# relays3.net
KiCad netlist of a schematic drawn in Altium Designer
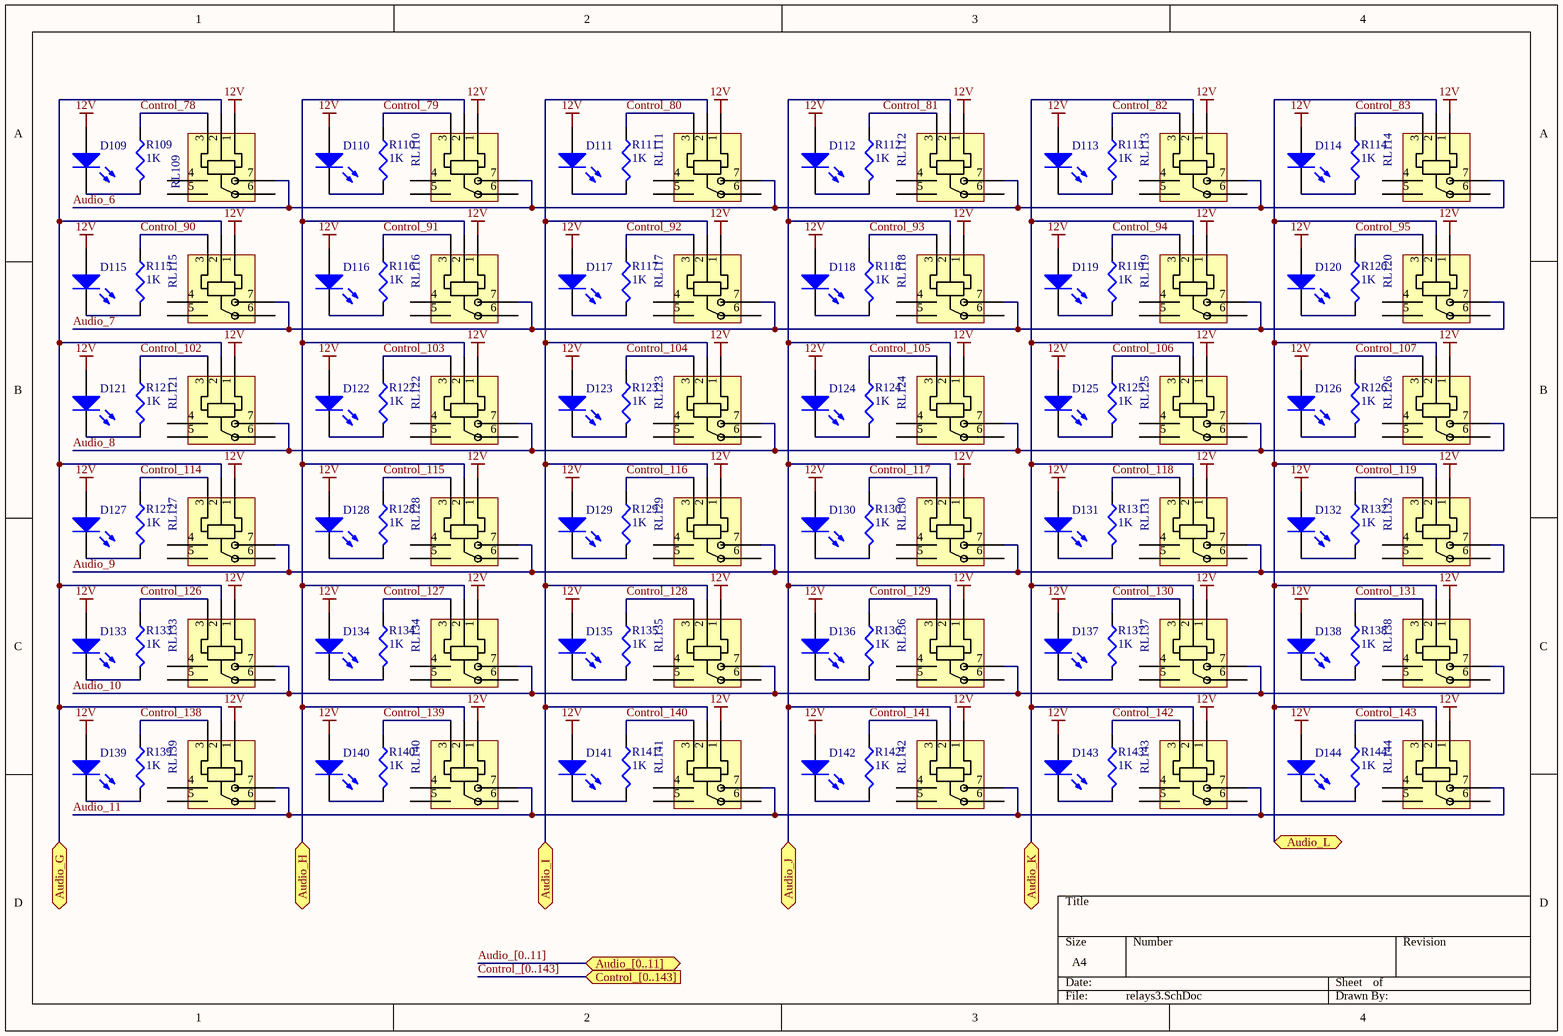
[diagram p0: relays3.SchDoc]

(export (version "E")
  (design (tool "Eeschema 10.0.6"))
  (components
    (comp (ref "D109")
      (value "LED0")
      (footprint "LED_round_5mm")
      (description "Typical INFRARED GaAs LED")
      (libsource (lib "Miscellaneous Devices") (part "LED0"))
    )
    (comp (ref "D110")
      (value "LED0")
      (footprint "LED_round_5mm")
      (description "Typical INFRARED GaAs LED")
      (libsource (lib "Miscellaneous Devices") (part "LED0"))
    )
    (comp (ref "D111")
      (value "LED0")
      (footprint "LED_round_5mm")
      (description "Typical INFRARED GaAs LED")
      (libsource (lib "Miscellaneous Devices") (part "LED0"))
    )
    (comp (ref "D112")
      (value "LED0")
      (footprint "LED_round_5mm")
      (description "Typical INFRARED GaAs LED")
      (libsource (lib "Miscellaneous Devices") (part "LED0"))
    )
    (comp (ref "D113")
      (value "LED0")
      (footprint "LED_round_5mm")
      (description "Typical INFRARED GaAs LED")
      (libsource (lib "Miscellaneous Devices") (part "LED0"))
    )
    (comp (ref "D114")
      (value "LED0")
      (footprint "LED_round_5mm")
      (description "Typical INFRARED GaAs LED")
      (libsource (lib "Miscellaneous Devices") (part "LED0"))
    )
    (comp (ref "D115")
      (value "LED0")
      (footprint "LED_round_5mm")
      (description "Typical INFRARED GaAs LED")
      (libsource (lib "Miscellaneous Devices") (part "LED0"))
    )
    (comp (ref "D116")
      (value "LED0")
      (footprint "LED_round_5mm")
      (description "Typical INFRARED GaAs LED")
      (libsource (lib "Miscellaneous Devices") (part "LED0"))
    )
    (comp (ref "D117")
      (value "LED0")
      (footprint "LED_round_5mm")
      (description "Typical INFRARED GaAs LED")
      (libsource (lib "Miscellaneous Devices") (part "LED0"))
    )
    (comp (ref "D118")
      (value "LED0")
      (footprint "LED_round_5mm")
      (description "Typical INFRARED GaAs LED")
      (libsource (lib "Miscellaneous Devices") (part "LED0"))
    )
    (comp (ref "D119")
      (value "LED0")
      (footprint "LED_round_5mm")
      (description "Typical INFRARED GaAs LED")
      (libsource (lib "Miscellaneous Devices") (part "LED0"))
    )
    (comp (ref "D120")
      (value "LED0")
      (footprint "LED_round_5mm")
      (description "Typical INFRARED GaAs LED")
      (libsource (lib "Miscellaneous Devices") (part "LED0"))
    )
    (comp (ref "D121")
      (value "LED0")
      (footprint "LED_round_5mm")
      (description "Typical INFRARED GaAs LED")
      (libsource (lib "Miscellaneous Devices") (part "LED0"))
    )
    (comp (ref "D122")
      (value "LED0")
      (footprint "LED_round_5mm")
      (description "Typical INFRARED GaAs LED")
      (libsource (lib "Miscellaneous Devices") (part "LED0"))
    )
    (comp (ref "D123")
      (value "LED0")
      (footprint "LED_round_5mm")
      (description "Typical INFRARED GaAs LED")
      (libsource (lib "Miscellaneous Devices") (part "LED0"))
    )
    (comp (ref "D124")
      (value "LED0")
      (footprint "LED_round_5mm")
      (description "Typical INFRARED GaAs LED")
      (libsource (lib "Miscellaneous Devices") (part "LED0"))
    )
    (comp (ref "D125")
      (value "LED0")
      (footprint "LED_round_5mm")
      (description "Typical INFRARED GaAs LED")
      (libsource (lib "Miscellaneous Devices") (part "LED0"))
    )
    (comp (ref "D126")
      (value "LED0")
      (footprint "LED_round_5mm")
      (description "Typical INFRARED GaAs LED")
      (libsource (lib "Miscellaneous Devices") (part "LED0"))
    )
    (comp (ref "D127")
      (value "LED0")
      (footprint "LED_round_5mm")
      (description "Typical INFRARED GaAs LED")
      (libsource (lib "Miscellaneous Devices") (part "LED0"))
    )
    (comp (ref "D128")
      (value "LED0")
      (footprint "LED_round_5mm")
      (description "Typical INFRARED GaAs LED")
      (libsource (lib "Miscellaneous Devices") (part "LED0"))
    )
    (comp (ref "D129")
      (value "LED0")
      (footprint "LED_round_5mm")
      (description "Typical INFRARED GaAs LED")
      (libsource (lib "Miscellaneous Devices") (part "LED0"))
    )
    (comp (ref "D130")
      (value "LED0")
      (footprint "LED_round_5mm")
      (description "Typical INFRARED GaAs LED")
      (libsource (lib "Miscellaneous Devices") (part "LED0"))
    )
    (comp (ref "D131")
      (value "LED0")
      (footprint "LED_round_5mm")
      (description "Typical INFRARED GaAs LED")
      (libsource (lib "Miscellaneous Devices") (part "LED0"))
    )
    (comp (ref "D132")
      (value "LED0")
      (footprint "LED_round_5mm")
      (description "Typical INFRARED GaAs LED")
      (libsource (lib "Miscellaneous Devices") (part "LED0"))
    )
    (comp (ref "D133")
      (value "LED0")
      (footprint "LED_round_5mm")
      (description "Typical INFRARED GaAs LED")
      (libsource (lib "Miscellaneous Devices") (part "LED0"))
    )
    (comp (ref "D134")
      (value "LED0")
      (footprint "LED_round_5mm")
      (description "Typical INFRARED GaAs LED")
      (libsource (lib "Miscellaneous Devices") (part "LED0"))
    )
    (comp (ref "D135")
      (value "LED0")
      (footprint "LED_round_5mm")
      (description "Typical INFRARED GaAs LED")
      (libsource (lib "Miscellaneous Devices") (part "LED0"))
    )
    (comp (ref "D136")
      (value "LED0")
      (footprint "LED_round_5mm")
      (description "Typical INFRARED GaAs LED")
      (libsource (lib "Miscellaneous Devices") (part "LED0"))
    )
    (comp (ref "D137")
      (value "LED0")
      (footprint "LED_round_5mm")
      (description "Typical INFRARED GaAs LED")
      (libsource (lib "Miscellaneous Devices") (part "LED0"))
    )
    (comp (ref "D138")
      (value "LED0")
      (footprint "LED_round_5mm")
      (description "Typical INFRARED GaAs LED")
      (libsource (lib "Miscellaneous Devices") (part "LED0"))
    )
    (comp (ref "D139")
      (value "LED0")
      (footprint "LED_round_5mm")
      (description "Typical INFRARED GaAs LED")
      (libsource (lib "Miscellaneous Devices") (part "LED0"))
    )
    (comp (ref "D140")
      (value "LED0")
      (footprint "LED_round_5mm")
      (description "Typical INFRARED GaAs LED")
      (libsource (lib "Miscellaneous Devices") (part "LED0"))
    )
    (comp (ref "D141")
      (value "LED0")
      (footprint "LED_round_5mm")
      (description "Typical INFRARED GaAs LED")
      (libsource (lib "Miscellaneous Devices") (part "LED0"))
    )
    (comp (ref "D142")
      (value "LED0")
      (footprint "LED_round_5mm")
      (description "Typical INFRARED GaAs LED")
      (libsource (lib "Miscellaneous Devices") (part "LED0"))
    )
    (comp (ref "D143")
      (value "LED0")
      (footprint "LED_round_5mm")
      (description "Typical INFRARED GaAs LED")
      (libsource (lib "Miscellaneous Devices") (part "LED0"))
    )
    (comp (ref "D144")
      (value "LED0")
      (footprint "LED_round_5mm")
      (description "Typical INFRARED GaAs LED")
      (libsource (lib "Miscellaneous Devices") (part "LED0"))
    )
    (comp (ref "R109")
      (value "1K")
      (footprint "J1-0603")
      (description "Resistor")
      (fields (field (name "Comment") "Res3"))
      (libsource (lib "Miscellaneous Devices") (part "Res3"))
    )
    (comp (ref "R110")
      (value "1K")
      (footprint "J1-0603")
      (description "Resistor")
      (fields (field (name "Comment") "Res3"))
      (libsource (lib "Miscellaneous Devices") (part "Res3"))
    )
    (comp (ref "R111")
      (value "1K")
      (footprint "J1-0603")
      (description "Resistor")
      (fields (field (name "Comment") "Res3"))
      (libsource (lib "Miscellaneous Devices") (part "Res3"))
    )
    (comp (ref "R112")
      (value "1K")
      (footprint "J1-0603")
      (description "Resistor")
      (fields (field (name "Comment") "Res3"))
      (libsource (lib "Miscellaneous Devices") (part "Res3"))
    )
    (comp (ref "R113")
      (value "1K")
      (footprint "J1-0603")
      (description "Resistor")
      (fields (field (name "Comment") "Res3"))
      (libsource (lib "Miscellaneous Devices") (part "Res3"))
    )
    (comp (ref "R114")
      (value "1K")
      (footprint "J1-0603")
      (description "Resistor")
      (fields (field (name "Comment") "Res3"))
      (libsource (lib "Miscellaneous Devices") (part "Res3"))
    )
    (comp (ref "R115")
      (value "1K")
      (footprint "J1-0603")
      (description "Resistor")
      (fields (field (name "Comment") "Res3"))
      (libsource (lib "Miscellaneous Devices") (part "Res3"))
    )
    (comp (ref "R116")
      (value "1K")
      (footprint "J1-0603")
      (description "Resistor")
      (fields (field (name "Comment") "Res3"))
      (libsource (lib "Miscellaneous Devices") (part "Res3"))
    )
    (comp (ref "R117")
      (value "1K")
      (footprint "J1-0603")
      (description "Resistor")
      (fields (field (name "Comment") "Res3"))
      (libsource (lib "Miscellaneous Devices") (part "Res3"))
    )
    (comp (ref "R118")
      (value "1K")
      (footprint "J1-0603")
      (description "Resistor")
      (fields (field (name "Comment") "Res3"))
      (libsource (lib "Miscellaneous Devices") (part "Res3"))
    )
    (comp (ref "R119")
      (value "1K")
      (footprint "J1-0603")
      (description "Resistor")
      (fields (field (name "Comment") "Res3"))
      (libsource (lib "Miscellaneous Devices") (part "Res3"))
    )
    (comp (ref "R120")
      (value "1K")
      (footprint "J1-0603")
      (description "Resistor")
      (fields (field (name "Comment") "Res3"))
      (libsource (lib "Miscellaneous Devices") (part "Res3"))
    )
    (comp (ref "R121")
      (value "1K")
      (footprint "J1-0603")
      (description "Resistor")
      (fields (field (name "Comment") "Res3"))
      (libsource (lib "Miscellaneous Devices") (part "Res3"))
    )
    (comp (ref "R122")
      (value "1K")
      (footprint "J1-0603")
      (description "Resistor")
      (fields (field (name "Comment") "Res3"))
      (libsource (lib "Miscellaneous Devices") (part "Res3"))
    )
    (comp (ref "R123")
      (value "1K")
      (footprint "J1-0603")
      (description "Resistor")
      (fields (field (name "Comment") "Res3"))
      (libsource (lib "Miscellaneous Devices") (part "Res3"))
    )
    (comp (ref "R124")
      (value "1K")
      (footprint "J1-0603")
      (description "Resistor")
      (fields (field (name "Comment") "Res3"))
      (libsource (lib "Miscellaneous Devices") (part "Res3"))
    )
    (comp (ref "R125")
      (value "1K")
      (footprint "J1-0603")
      (description "Resistor")
      (fields (field (name "Comment") "Res3"))
      (libsource (lib "Miscellaneous Devices") (part "Res3"))
    )
    (comp (ref "R126")
      (value "1K")
      (footprint "J1-0603")
      (description "Resistor")
      (fields (field (name "Comment") "Res3"))
      (libsource (lib "Miscellaneous Devices") (part "Res3"))
    )
    (comp (ref "R127")
      (value "1K")
      (footprint "J1-0603")
      (description "Resistor")
      (fields (field (name "Comment") "Res3"))
      (libsource (lib "Miscellaneous Devices") (part "Res3"))
    )
    (comp (ref "R128")
      (value "1K")
      (footprint "J1-0603")
      (description "Resistor")
      (fields (field (name "Comment") "Res3"))
      (libsource (lib "Miscellaneous Devices") (part "Res3"))
    )
    (comp (ref "R129")
      (value "1K")
      (footprint "J1-0603")
      (description "Resistor")
      (fields (field (name "Comment") "Res3"))
      (libsource (lib "Miscellaneous Devices") (part "Res3"))
    )
    (comp (ref "R130")
      (value "1K")
      (footprint "J1-0603")
      (description "Resistor")
      (fields (field (name "Comment") "Res3"))
      (libsource (lib "Miscellaneous Devices") (part "Res3"))
    )
    (comp (ref "R131")
      (value "1K")
      (footprint "J1-0603")
      (description "Resistor")
      (fields (field (name "Comment") "Res3"))
      (libsource (lib "Miscellaneous Devices") (part "Res3"))
    )
    (comp (ref "R132")
      (value "1K")
      (footprint "J1-0603")
      (description "Resistor")
      (fields (field (name "Comment") "Res3"))
      (libsource (lib "Miscellaneous Devices") (part "Res3"))
    )
    (comp (ref "R133")
      (value "1K")
      (footprint "J1-0603")
      (description "Resistor")
      (fields (field (name "Comment") "Res3"))
      (libsource (lib "Miscellaneous Devices") (part "Res3"))
    )
    (comp (ref "R134")
      (value "1K")
      (footprint "J1-0603")
      (description "Resistor")
      (fields (field (name "Comment") "Res3"))
      (libsource (lib "Miscellaneous Devices") (part "Res3"))
    )
    (comp (ref "R135")
      (value "1K")
      (footprint "J1-0603")
      (description "Resistor")
      (fields (field (name "Comment") "Res3"))
      (libsource (lib "Miscellaneous Devices") (part "Res3"))
    )
    (comp (ref "R136")
      (value "1K")
      (footprint "J1-0603")
      (description "Resistor")
      (fields (field (name "Comment") "Res3"))
      (libsource (lib "Miscellaneous Devices") (part "Res3"))
    )
    (comp (ref "R137")
      (value "1K")
      (footprint "J1-0603")
      (description "Resistor")
      (fields (field (name "Comment") "Res3"))
      (libsource (lib "Miscellaneous Devices") (part "Res3"))
    )
    (comp (ref "R138")
      (value "1K")
      (footprint "J1-0603")
      (description "Resistor")
      (fields (field (name "Comment") "Res3"))
      (libsource (lib "Miscellaneous Devices") (part "Res3"))
    )
    (comp (ref "R139")
      (value "1K")
      (footprint "J1-0603")
      (description "Resistor")
      (fields (field (name "Comment") "Res3"))
      (libsource (lib "Miscellaneous Devices") (part "Res3"))
    )
    (comp (ref "R140")
      (value "1K")
      (footprint "J1-0603")
      (description "Resistor")
      (fields (field (name "Comment") "Res3"))
      (libsource (lib "Miscellaneous Devices") (part "Res3"))
    )
    (comp (ref "R141")
      (value "1K")
      (footprint "J1-0603")
      (description "Resistor")
      (fields (field (name "Comment") "Res3"))
      (libsource (lib "Miscellaneous Devices") (part "Res3"))
    )
    (comp (ref "R142")
      (value "1K")
      (footprint "J1-0603")
      (description "Resistor")
      (fields (field (name "Comment") "Res3"))
      (libsource (lib "Miscellaneous Devices") (part "Res3"))
    )
    (comp (ref "R143")
      (value "1K")
      (footprint "J1-0603")
      (description "Resistor")
      (fields (field (name "Comment") "Res3"))
      (libsource (lib "Miscellaneous Devices") (part "Res3"))
    )
    (comp (ref "R144")
      (value "1K")
      (footprint "J1-0603")
      (description "Resistor")
      (fields (field (name "Comment") "Res3"))
      (libsource (lib "Miscellaneous Devices") (part "Res3"))
    )
    (comp (ref "RL109")
      (value "Relay")
      (footprint "Relay_FRA3")
      (description "Miniature power relay")
      (fields (field (name "PART NUMBER") "FRA3C-DC12"))
      (libsource (lib "tech-thing") (part "Relay_FRA3"))
    )
    (comp (ref "RL110")
      (value "Relay")
      (footprint "Relay_FRA3")
      (description "Miniature power relay")
      (fields (field (name "PART NUMBER") "FRA3C-DC12"))
      (libsource (lib "tech-thing") (part "Relay_FRA3"))
    )
    (comp (ref "RL111")
      (value "Relay")
      (footprint "Relay_FRA3")
      (description "Miniature power relay")
      (fields (field (name "PART NUMBER") "FRA3C-DC12"))
      (libsource (lib "tech-thing") (part "Relay_FRA3"))
    )
    (comp (ref "RL112")
      (value "Relay")
      (footprint "Relay_FRA3")
      (description "Miniature power relay")
      (fields (field (name "PART NUMBER") "FRA3C-DC12"))
      (libsource (lib "tech-thing") (part "Relay_FRA3"))
    )
    (comp (ref "RL113")
      (value "Relay")
      (footprint "Relay_FRA3")
      (description "Miniature power relay")
      (fields (field (name "PART NUMBER") "FRA3C-DC12"))
      (libsource (lib "tech-thing") (part "Relay_FRA3"))
    )
    (comp (ref "RL114")
      (value "Relay")
      (footprint "Relay_FRA3")
      (description "Miniature power relay")
      (fields (field (name "PART NUMBER") "FRA3C-DC12"))
      (libsource (lib "tech-thing") (part "Relay_FRA3"))
    )
    (comp (ref "RL115")
      (value "Relay")
      (footprint "Relay_FRA3")
      (description "Miniature power relay")
      (fields (field (name "PART NUMBER") "FRA3C-DC12"))
      (libsource (lib "tech-thing") (part "Relay_FRA3"))
    )
    (comp (ref "RL116")
      (value "Relay")
      (footprint "Relay_FRA3")
      (description "Miniature power relay")
      (fields (field (name "PART NUMBER") "FRA3C-DC12"))
      (libsource (lib "tech-thing") (part "Relay_FRA3"))
    )
    (comp (ref "RL117")
      (value "Relay")
      (footprint "Relay_FRA3")
      (description "Miniature power relay")
      (fields (field (name "PART NUMBER") "FRA3C-DC12"))
      (libsource (lib "tech-thing") (part "Relay_FRA3"))
    )
    (comp (ref "RL118")
      (value "Relay")
      (footprint "Relay_FRA3")
      (description "Miniature power relay")
      (fields (field (name "PART NUMBER") "FRA3C-DC12"))
      (libsource (lib "tech-thing") (part "Relay_FRA3"))
    )
    (comp (ref "RL119")
      (value "Relay")
      (footprint "Relay_FRA3")
      (description "Miniature power relay")
      (fields (field (name "PART NUMBER") "FRA3C-DC12"))
      (libsource (lib "tech-thing") (part "Relay_FRA3"))
    )
    (comp (ref "RL120")
      (value "Relay")
      (footprint "Relay_FRA3")
      (description "Miniature power relay")
      (fields (field (name "PART NUMBER") "FRA3C-DC12"))
      (libsource (lib "tech-thing") (part "Relay_FRA3"))
    )
    (comp (ref "RL121")
      (value "Relay")
      (footprint "Relay_FRA3")
      (description "Miniature power relay")
      (fields (field (name "PART NUMBER") "FRA3C-DC12"))
      (libsource (lib "tech-thing") (part "Relay_FRA3"))
    )
    (comp (ref "RL122")
      (value "Relay")
      (footprint "Relay_FRA3")
      (description "Miniature power relay")
      (fields (field (name "PART NUMBER") "FRA3C-DC12"))
      (libsource (lib "tech-thing") (part "Relay_FRA3"))
    )
    (comp (ref "RL123")
      (value "Relay")
      (footprint "Relay_FRA3")
      (description "Miniature power relay")
      (fields (field (name "PART NUMBER") "FRA3C-DC12"))
      (libsource (lib "tech-thing") (part "Relay_FRA3"))
    )
    (comp (ref "RL124")
      (value "Relay")
      (footprint "Relay_FRA3")
      (description "Miniature power relay")
      (fields (field (name "PART NUMBER") "FRA3C-DC12"))
      (libsource (lib "tech-thing") (part "Relay_FRA3"))
    )
    (comp (ref "RL125")
      (value "Relay")
      (footprint "Relay_FRA3")
      (description "Miniature power relay")
      (fields (field (name "PART NUMBER") "FRA3C-DC12"))
      (libsource (lib "tech-thing") (part "Relay_FRA3"))
    )
    (comp (ref "RL126")
      (value "Relay")
      (footprint "Relay_FRA3")
      (description "Miniature power relay")
      (fields (field (name "PART NUMBER") "FRA3C-DC12"))
      (libsource (lib "tech-thing") (part "Relay_FRA3"))
    )
    (comp (ref "RL127")
      (value "Relay")
      (footprint "Relay_FRA3")
      (description "Miniature power relay")
      (fields (field (name "PART NUMBER") "FRA3C-DC12"))
      (libsource (lib "tech-thing") (part "Relay_FRA3"))
    )
    (comp (ref "RL128")
      (value "Relay")
      (footprint "Relay_FRA3")
      (description "Miniature power relay")
      (fields (field (name "PART NUMBER") "FRA3C-DC12"))
      (libsource (lib "tech-thing") (part "Relay_FRA3"))
    )
    (comp (ref "RL129")
      (value "Relay")
      (footprint "Relay_FRA3")
      (description "Miniature power relay")
      (fields (field (name "PART NUMBER") "FRA3C-DC12"))
      (libsource (lib "tech-thing") (part "Relay_FRA3"))
    )
    (comp (ref "RL130")
      (value "Relay")
      (footprint "Relay_FRA3")
      (description "Miniature power relay")
      (fields (field (name "PART NUMBER") "FRA3C-DC12"))
      (libsource (lib "tech-thing") (part "Relay_FRA3"))
    )
    (comp (ref "RL131")
      (value "Relay")
      (footprint "Relay_FRA3")
      (description "Miniature power relay")
      (fields (field (name "PART NUMBER") "FRA3C-DC12"))
      (libsource (lib "tech-thing") (part "Relay_FRA3"))
    )
    (comp (ref "RL132")
      (value "Relay")
      (footprint "Relay_FRA3")
      (description "Miniature power relay")
      (fields (field (name "PART NUMBER") "FRA3C-DC12"))
      (libsource (lib "tech-thing") (part "Relay_FRA3"))
    )
    (comp (ref "RL133")
      (value "Relay")
      (footprint "Relay_FRA3")
      (description "Miniature power relay")
      (fields (field (name "PART NUMBER") "FRA3C-DC12"))
      (libsource (lib "tech-thing") (part "Relay_FRA3"))
    )
    (comp (ref "RL134")
      (value "Relay")
      (footprint "Relay_FRA3")
      (description "Miniature power relay")
      (fields (field (name "PART NUMBER") "FRA3C-DC12"))
      (libsource (lib "tech-thing") (part "Relay_FRA3"))
    )
    (comp (ref "RL135")
      (value "Relay")
      (footprint "Relay_FRA3")
      (description "Miniature power relay")
      (fields (field (name "PART NUMBER") "FRA3C-DC12"))
      (libsource (lib "tech-thing") (part "Relay_FRA3"))
    )
    (comp (ref "RL136")
      (value "Relay")
      (footprint "Relay_FRA3")
      (description "Miniature power relay")
      (fields (field (name "PART NUMBER") "FRA3C-DC12"))
      (libsource (lib "tech-thing") (part "Relay_FRA3"))
    )
    (comp (ref "RL137")
      (value "Relay")
      (footprint "Relay_FRA3")
      (description "Miniature power relay")
      (fields (field (name "PART NUMBER") "FRA3C-DC12"))
      (libsource (lib "tech-thing") (part "Relay_FRA3"))
    )
    (comp (ref "RL138")
      (value "Relay")
      (footprint "Relay_FRA3")
      (description "Miniature power relay")
      (fields (field (name "PART NUMBER") "FRA3C-DC12"))
      (libsource (lib "tech-thing") (part "Relay_FRA3"))
    )
    (comp (ref "RL139")
      (value "Relay")
      (footprint "Relay_FRA3")
      (description "Miniature power relay")
      (fields (field (name "PART NUMBER") "FRA3C-DC12"))
      (libsource (lib "tech-thing") (part "Relay_FRA3"))
    )
    (comp (ref "RL140")
      (value "Relay")
      (footprint "Relay_FRA3")
      (description "Miniature power relay")
      (fields (field (name "PART NUMBER") "FRA3C-DC12"))
      (libsource (lib "tech-thing") (part "Relay_FRA3"))
    )
    (comp (ref "RL141")
      (value "Relay")
      (footprint "Relay_FRA3")
      (description "Miniature power relay")
      (fields (field (name "PART NUMBER") "FRA3C-DC12"))
      (libsource (lib "tech-thing") (part "Relay_FRA3"))
    )
    (comp (ref "RL142")
      (value "Relay")
      (footprint "Relay_FRA3")
      (description "Miniature power relay")
      (fields (field (name "PART NUMBER") "FRA3C-DC12"))
      (libsource (lib "tech-thing") (part "Relay_FRA3"))
    )
    (comp (ref "RL143")
      (value "Relay")
      (footprint "Relay_FRA3")
      (description "Miniature power relay")
      (fields (field (name "PART NUMBER") "FRA3C-DC12"))
      (libsource (lib "tech-thing") (part "Relay_FRA3"))
    )
    (comp (ref "RL144")
      (value "Relay")
      (footprint "Relay_FRA3")
      (description "Miniature power relay")
      (fields (field (name "PART NUMBER") "FRA3C-DC12"))
      (libsource (lib "tech-thing") (part "Relay_FRA3"))
    )
  )
  (nets
    (net (code "115") (name "/Audio_6") (class "Default")
      (node (ref "RL109") (pin "7") (pintype "passive"))
      (node (ref "RL110") (pin "7") (pintype "passive"))
      (node (ref "RL111") (pin "7") (pintype "passive"))
      (node (ref "RL112") (pin "7") (pintype "passive"))
      (node (ref "RL113") (pin "7") (pintype "passive"))
      (node (ref "RL114") (pin "7") (pintype "passive"))
    )
    (net (code "116") (name "/Audio_7") (class "Default")
      (node (ref "RL115") (pin "7") (pintype "passive"))
      (node (ref "RL116") (pin "7") (pintype "passive"))
      (node (ref "RL117") (pin "7") (pintype "passive"))
      (node (ref "RL118") (pin "7") (pintype "passive"))
      (node (ref "RL119") (pin "7") (pintype "passive"))
      (node (ref "RL120") (pin "7") (pintype "passive"))
    )
    (net (code "117") (name "/Audio_8") (class "Default")
      (node (ref "RL121") (pin "7") (pintype "passive"))
      (node (ref "RL122") (pin "7") (pintype "passive"))
      (node (ref "RL123") (pin "7") (pintype "passive"))
      (node (ref "RL124") (pin "7") (pintype "passive"))
      (node (ref "RL125") (pin "7") (pintype "passive"))
      (node (ref "RL126") (pin "7") (pintype "passive"))
    )
    (net (code "118") (name "/Audio_9") (class "Default")
      (node (ref "RL127") (pin "7") (pintype "passive"))
      (node (ref "RL128") (pin "7") (pintype "passive"))
      (node (ref "RL129") (pin "7") (pintype "passive"))
      (node (ref "RL130") (pin "7") (pintype "passive"))
      (node (ref "RL131") (pin "7") (pintype "passive"))
      (node (ref "RL132") (pin "7") (pintype "passive"))
    )
    (net (code "119") (name "/Audio_10") (class "Default")
      (node (ref "RL133") (pin "7") (pintype "passive"))
      (node (ref "RL134") (pin "7") (pintype "passive"))
      (node (ref "RL135") (pin "7") (pintype "passive"))
      (node (ref "RL136") (pin "7") (pintype "passive"))
      (node (ref "RL137") (pin "7") (pintype "passive"))
      (node (ref "RL138") (pin "7") (pintype "passive"))
    )
    (net (code "120") (name "/Audio_11") (class "Default")
      (node (ref "RL139") (pin "7") (pintype "passive"))
      (node (ref "RL140") (pin "7") (pintype "passive"))
      (node (ref "RL141") (pin "7") (pintype "passive"))
      (node (ref "RL142") (pin "7") (pintype "passive"))
      (node (ref "RL143") (pin "7") (pintype "passive"))
      (node (ref "RL144") (pin "7") (pintype "passive"))
    )
    (net (code "121") (name "/Audio_G") (class "Default")
      (node (ref "RL109") (pin "2") (pintype "passive"))
      (node (ref "RL115") (pin "2") (pintype "passive"))
      (node (ref "RL121") (pin "2") (pintype "passive"))
      (node (ref "RL127") (pin "2") (pintype "passive"))
      (node (ref "RL133") (pin "2") (pintype "passive"))
      (node (ref "RL139") (pin "2") (pintype "passive"))
    )
    (net (code "122") (name "/Audio_H") (class "Default")
      (node (ref "RL110") (pin "2") (pintype "passive"))
      (node (ref "RL116") (pin "2") (pintype "passive"))
      (node (ref "RL122") (pin "2") (pintype "passive"))
      (node (ref "RL128") (pin "2") (pintype "passive"))
      (node (ref "RL134") (pin "2") (pintype "passive"))
      (node (ref "RL140") (pin "2") (pintype "passive"))
    )
    (net (code "123") (name "/Audio_I") (class "Default")
      (node (ref "RL111") (pin "2") (pintype "passive"))
      (node (ref "RL117") (pin "2") (pintype "passive"))
      (node (ref "RL123") (pin "2") (pintype "passive"))
      (node (ref "RL129") (pin "2") (pintype "passive"))
      (node (ref "RL135") (pin "2") (pintype "passive"))
      (node (ref "RL141") (pin "2") (pintype "passive"))
    )
    (net (code "124") (name "/Audio_J") (class "Default")
      (node (ref "RL112") (pin "2") (pintype "passive"))
      (node (ref "RL118") (pin "2") (pintype "passive"))
      (node (ref "RL124") (pin "2") (pintype "passive"))
      (node (ref "RL130") (pin "2") (pintype "passive"))
      (node (ref "RL136") (pin "2") (pintype "passive"))
      (node (ref "RL142") (pin "2") (pintype "passive"))
    )
    (net (code "125") (name "/Audio_K") (class "Default")
      (node (ref "RL113") (pin "2") (pintype "passive"))
      (node (ref "RL119") (pin "2") (pintype "passive"))
      (node (ref "RL125") (pin "2") (pintype "passive"))
      (node (ref "RL131") (pin "2") (pintype "passive"))
      (node (ref "RL137") (pin "2") (pintype "passive"))
      (node (ref "RL143") (pin "2") (pintype "passive"))
    )
    (net (code "126") (name "/Audio_L") (class "Default")
      (node (ref "RL114") (pin "2") (pintype "passive"))
      (node (ref "RL120") (pin "2") (pintype "passive"))
      (node (ref "RL126") (pin "2") (pintype "passive"))
      (node (ref "RL132") (pin "2") (pintype "passive"))
      (node (ref "RL138") (pin "2") (pintype "passive"))
      (node (ref "RL144") (pin "2") (pintype "passive"))
    )
    (net (code "128") (name "/Control_78") (class "Default")
      (node (ref "R109") (pin "1") (pinfunction "1_1") (pintype "passive"))
      (node (ref "RL109") (pin "3") (pintype "passive"))
    )
    (net (code "129") (name "/Control_79") (class "Default")
      (node (ref "R110") (pin "1") (pinfunction "1_1") (pintype "passive"))
      (node (ref "RL110") (pin "3") (pintype "passive"))
    )
    (net (code "130") (name "/Control_80") (class "Default")
      (node (ref "R111") (pin "1") (pinfunction "1_1") (pintype "passive"))
      (node (ref "RL111") (pin "3") (pintype "passive"))
    )
    (net (code "131") (name "/Control_81") (class "Default")
      (node (ref "R112") (pin "1") (pinfunction "1_1") (pintype "passive"))
      (node (ref "RL112") (pin "3") (pintype "passive"))
    )
    (net (code "132") (name "/Control_82") (class "Default")
      (node (ref "R113") (pin "1") (pinfunction "1_1") (pintype "passive"))
      (node (ref "RL113") (pin "3") (pintype "passive"))
    )
    (net (code "133") (name "/Control_83") (class "Default")
      (node (ref "R114") (pin "1") (pinfunction "1_1") (pintype "passive"))
      (node (ref "RL114") (pin "3") (pintype "passive"))
    )
    (net (code "134") (name "/Control_90") (class "Default")
      (node (ref "R115") (pin "1") (pinfunction "1_1") (pintype "passive"))
      (node (ref "RL115") (pin "3") (pintype "passive"))
    )
    (net (code "135") (name "/Control_91") (class "Default")
      (node (ref "R116") (pin "1") (pinfunction "1_1") (pintype "passive"))
      (node (ref "RL116") (pin "3") (pintype "passive"))
    )
    (net (code "136") (name "/Control_92") (class "Default")
      (node (ref "R117") (pin "1") (pinfunction "1_1") (pintype "passive"))
      (node (ref "RL117") (pin "3") (pintype "passive"))
    )
    (net (code "137") (name "/Control_93") (class "Default")
      (node (ref "R118") (pin "1") (pinfunction "1_1") (pintype "passive"))
      (node (ref "RL118") (pin "3") (pintype "passive"))
    )
    (net (code "138") (name "/Control_94") (class "Default")
      (node (ref "R119") (pin "1") (pinfunction "1_1") (pintype "passive"))
      (node (ref "RL119") (pin "3") (pintype "passive"))
    )
    (net (code "139") (name "/Control_95") (class "Default")
      (node (ref "R120") (pin "1") (pinfunction "1_1") (pintype "passive"))
      (node (ref "RL120") (pin "3") (pintype "passive"))
    )
    (net (code "140") (name "/Control_102") (class "Default")
      (node (ref "R121") (pin "1") (pinfunction "1_1") (pintype "passive"))
      (node (ref "RL121") (pin "3") (pintype "passive"))
    )
    (net (code "141") (name "/Control_103") (class "Default")
      (node (ref "R122") (pin "1") (pinfunction "1_1") (pintype "passive"))
      (node (ref "RL122") (pin "3") (pintype "passive"))
    )
    (net (code "142") (name "/Control_104") (class "Default")
      (node (ref "R123") (pin "1") (pinfunction "1_1") (pintype "passive"))
      (node (ref "RL123") (pin "3") (pintype "passive"))
    )
    (net (code "143") (name "/Control_105") (class "Default")
      (node (ref "R124") (pin "1") (pinfunction "1_1") (pintype "passive"))
      (node (ref "RL124") (pin "3") (pintype "passive"))
    )
    (net (code "144") (name "/Control_106") (class "Default")
      (node (ref "R125") (pin "1") (pinfunction "1_1") (pintype "passive"))
      (node (ref "RL125") (pin "3") (pintype "passive"))
    )
    (net (code "145") (name "/Control_107") (class "Default")
      (node (ref "R126") (pin "1") (pinfunction "1_1") (pintype "passive"))
      (node (ref "RL126") (pin "3") (pintype "passive"))
    )
    (net (code "146") (name "/Control_114") (class "Default")
      (node (ref "R127") (pin "1") (pinfunction "1_1") (pintype "passive"))
      (node (ref "RL127") (pin "3") (pintype "passive"))
    )
    (net (code "147") (name "/Control_115") (class "Default")
      (node (ref "R128") (pin "1") (pinfunction "1_1") (pintype "passive"))
      (node (ref "RL128") (pin "3") (pintype "passive"))
    )
    (net (code "148") (name "/Control_116") (class "Default")
      (node (ref "R129") (pin "1") (pinfunction "1_1") (pintype "passive"))
      (node (ref "RL129") (pin "3") (pintype "passive"))
    )
    (net (code "149") (name "/Control_117") (class "Default")
      (node (ref "R130") (pin "1") (pinfunction "1_1") (pintype "passive"))
      (node (ref "RL130") (pin "3") (pintype "passive"))
    )
    (net (code "150") (name "/Control_118") (class "Default")
      (node (ref "R131") (pin "1") (pinfunction "1_1") (pintype "passive"))
      (node (ref "RL131") (pin "3") (pintype "passive"))
    )
    (net (code "151") (name "/Control_119") (class "Default")
      (node (ref "R132") (pin "1") (pinfunction "1_1") (pintype "passive"))
      (node (ref "RL132") (pin "3") (pintype "passive"))
    )
    (net (code "152") (name "/Control_126") (class "Default")
      (node (ref "R133") (pin "1") (pinfunction "1_1") (pintype "passive"))
      (node (ref "RL133") (pin "3") (pintype "passive"))
    )
    (net (code "153") (name "/Control_127") (class "Default")
      (node (ref "R134") (pin "1") (pinfunction "1_1") (pintype "passive"))
      (node (ref "RL134") (pin "3") (pintype "passive"))
    )
    (net (code "154") (name "/Control_128") (class "Default")
      (node (ref "R135") (pin "1") (pinfunction "1_1") (pintype "passive"))
      (node (ref "RL135") (pin "3") (pintype "passive"))
    )
    (net (code "155") (name "/Control_129") (class "Default")
      (node (ref "R136") (pin "1") (pinfunction "1_1") (pintype "passive"))
      (node (ref "RL136") (pin "3") (pintype "passive"))
    )
    (net (code "156") (name "/Control_130") (class "Default")
      (node (ref "R137") (pin "1") (pinfunction "1_1") (pintype "passive"))
      (node (ref "RL137") (pin "3") (pintype "passive"))
    )
    (net (code "157") (name "/Control_131") (class "Default")
      (node (ref "R138") (pin "1") (pinfunction "1_1") (pintype "passive"))
      (node (ref "RL138") (pin "3") (pintype "passive"))
    )
    (net (code "158") (name "/Control_138") (class "Default")
      (node (ref "R139") (pin "1") (pinfunction "1_1") (pintype "passive"))
      (node (ref "RL139") (pin "3") (pintype "passive"))
    )
    (net (code "159") (name "/Control_139") (class "Default")
      (node (ref "R140") (pin "1") (pinfunction "1_1") (pintype "passive"))
      (node (ref "RL140") (pin "3") (pintype "passive"))
    )
    (net (code "160") (name "/Control_140") (class "Default")
      (node (ref "R141") (pin "1") (pinfunction "1_1") (pintype "passive"))
      (node (ref "RL141") (pin "3") (pintype "passive"))
    )
    (net (code "161") (name "/Control_141") (class "Default")
      (node (ref "R142") (pin "1") (pinfunction "1_1") (pintype "passive"))
      (node (ref "RL142") (pin "3") (pintype "passive"))
    )
    (net (code "162") (name "/Control_142") (class "Default")
      (node (ref "R143") (pin "1") (pinfunction "1_1") (pintype "passive"))
      (node (ref "RL143") (pin "3") (pintype "passive"))
    )
    (net (code "163") (name "/Control_143") (class "Default")
      (node (ref "R144") (pin "1") (pinfunction "1_1") (pintype "passive"))
      (node (ref "RL144") (pin "3") (pintype "passive"))
    )
    (net (code "165") (name "12V") (class "Default")
      (node (ref "D109") (pin "1") (pinfunction "A_1") (pintype "passive"))
      (node (ref "D110") (pin "1") (pinfunction "A_1") (pintype "passive"))
      (node (ref "D111") (pin "1") (pinfunction "A_1") (pintype "passive"))
      (node (ref "D112") (pin "1") (pinfunction "A_1") (pintype "passive"))
      (node (ref "D113") (pin "1") (pinfunction "A_1") (pintype "passive"))
      (node (ref "D114") (pin "1") (pinfunction "A_1") (pintype "passive"))
      (node (ref "D115") (pin "1") (pinfunction "A_1") (pintype "passive"))
      (node (ref "D116") (pin "1") (pinfunction "A_1") (pintype "passive"))
      (node (ref "D117") (pin "1") (pinfunction "A_1") (pintype "passive"))
      (node (ref "D118") (pin "1") (pinfunction "A_1") (pintype "passive"))
      (node (ref "D119") (pin "1") (pinfunction "A_1") (pintype "passive"))
      (node (ref "D120") (pin "1") (pinfunction "A_1") (pintype "passive"))
      (node (ref "D121") (pin "1") (pinfunction "A_1") (pintype "passive"))
      (node (ref "D122") (pin "1") (pinfunction "A_1") (pintype "passive"))
      (node (ref "D123") (pin "1") (pinfunction "A_1") (pintype "passive"))
      (node (ref "D124") (pin "1") (pinfunction "A_1") (pintype "passive"))
      (node (ref "D125") (pin "1") (pinfunction "A_1") (pintype "passive"))
      (node (ref "D126") (pin "1") (pinfunction "A_1") (pintype "passive"))
      (node (ref "D127") (pin "1") (pinfunction "A_1") (pintype "passive"))
      (node (ref "D128") (pin "1") (pinfunction "A_1") (pintype "passive"))
      (node (ref "D129") (pin "1") (pinfunction "A_1") (pintype "passive"))
      (node (ref "D130") (pin "1") (pinfunction "A_1") (pintype "passive"))
      (node (ref "D131") (pin "1") (pinfunction "A_1") (pintype "passive"))
      (node (ref "D132") (pin "1") (pinfunction "A_1") (pintype "passive"))
      (node (ref "D133") (pin "1") (pinfunction "A_1") (pintype "passive"))
      (node (ref "D134") (pin "1") (pinfunction "A_1") (pintype "passive"))
      (node (ref "D135") (pin "1") (pinfunction "A_1") (pintype "passive"))
      (node (ref "D136") (pin "1") (pinfunction "A_1") (pintype "passive"))
      (node (ref "D137") (pin "1") (pinfunction "A_1") (pintype "passive"))
      (node (ref "D138") (pin "1") (pinfunction "A_1") (pintype "passive"))
      (node (ref "D139") (pin "1") (pinfunction "A_1") (pintype "passive"))
      (node (ref "D140") (pin "1") (pinfunction "A_1") (pintype "passive"))
      (node (ref "D141") (pin "1") (pinfunction "A_1") (pintype "passive"))
      (node (ref "D142") (pin "1") (pinfunction "A_1") (pintype "passive"))
      (node (ref "D143") (pin "1") (pinfunction "A_1") (pintype "passive"))
      (node (ref "D144") (pin "1") (pinfunction "A_1") (pintype "passive"))
      (node (ref "RL109") (pin "1") (pintype "passive"))
      (node (ref "RL110") (pin "1") (pintype "passive"))
      (node (ref "RL111") (pin "1") (pintype "passive"))
      (node (ref "RL112") (pin "1") (pintype "passive"))
      (node (ref "RL113") (pin "1") (pintype "passive"))
      (node (ref "RL114") (pin "1") (pintype "passive"))
      (node (ref "RL115") (pin "1") (pintype "passive"))
      (node (ref "RL116") (pin "1") (pintype "passive"))
      (node (ref "RL117") (pin "1") (pintype "passive"))
      (node (ref "RL118") (pin "1") (pintype "passive"))
      (node (ref "RL119") (pin "1") (pintype "passive"))
      (node (ref "RL120") (pin "1") (pintype "passive"))
      (node (ref "RL121") (pin "1") (pintype "passive"))
      (node (ref "RL122") (pin "1") (pintype "passive"))
      (node (ref "RL123") (pin "1") (pintype "passive"))
      (node (ref "RL124") (pin "1") (pintype "passive"))
      (node (ref "RL125") (pin "1") (pintype "passive"))
      (node (ref "RL126") (pin "1") (pintype "passive"))
      (node (ref "RL127") (pin "1") (pintype "passive"))
      (node (ref "RL128") (pin "1") (pintype "passive"))
      (node (ref "RL129") (pin "1") (pintype "passive"))
      (node (ref "RL130") (pin "1") (pintype "passive"))
      (node (ref "RL131") (pin "1") (pintype "passive"))
      (node (ref "RL132") (pin "1") (pintype "passive"))
      (node (ref "RL133") (pin "1") (pintype "passive"))
      (node (ref "RL134") (pin "1") (pintype "passive"))
      (node (ref "RL135") (pin "1") (pintype "passive"))
      (node (ref "RL136") (pin "1") (pintype "passive"))
      (node (ref "RL137") (pin "1") (pintype "passive"))
      (node (ref "RL138") (pin "1") (pintype "passive"))
      (node (ref "RL139") (pin "1") (pintype "passive"))
      (node (ref "RL140") (pin "1") (pintype "passive"))
      (node (ref "RL141") (pin "1") (pintype "passive"))
      (node (ref "RL142") (pin "1") (pintype "passive"))
      (node (ref "RL143") (pin "1") (pintype "passive"))
      (node (ref "RL144") (pin "1") (pintype "passive"))
    )
    (net (code "166") (name "Net-(D109-K)") (class "Default")
      (node (ref "D109") (pin "2") (pinfunction "K_2") (pintype "passive"))
      (node (ref "R109") (pin "2") (pinfunction "2_2") (pintype "passive"))
    )
    (net (code "167") (name "Net-(D110-K)") (class "Default")
      (node (ref "D110") (pin "2") (pinfunction "K_2") (pintype "passive"))
      (node (ref "R110") (pin "2") (pinfunction "2_2") (pintype "passive"))
    )
    (net (code "168") (name "Net-(D111-K)") (class "Default")
      (node (ref "D111") (pin "2") (pinfunction "K_2") (pintype "passive"))
      (node (ref "R111") (pin "2") (pinfunction "2_2") (pintype "passive"))
    )
    (net (code "169") (name "Net-(D112-K)") (class "Default")
      (node (ref "D112") (pin "2") (pinfunction "K_2") (pintype "passive"))
      (node (ref "R112") (pin "2") (pinfunction "2_2") (pintype "passive"))
    )
    (net (code "170") (name "Net-(D113-K)") (class "Default")
      (node (ref "D113") (pin "2") (pinfunction "K_2") (pintype "passive"))
      (node (ref "R113") (pin "2") (pinfunction "2_2") (pintype "passive"))
    )
    (net (code "171") (name "Net-(D114-K)") (class "Default")
      (node (ref "D114") (pin "2") (pinfunction "K_2") (pintype "passive"))
      (node (ref "R114") (pin "2") (pinfunction "2_2") (pintype "passive"))
    )
    (net (code "172") (name "Net-(D115-K)") (class "Default")
      (node (ref "D115") (pin "2") (pinfunction "K_2") (pintype "passive"))
      (node (ref "R115") (pin "2") (pinfunction "2_2") (pintype "passive"))
    )
    (net (code "173") (name "Net-(D116-K)") (class "Default")
      (node (ref "D116") (pin "2") (pinfunction "K_2") (pintype "passive"))
      (node (ref "R116") (pin "2") (pinfunction "2_2") (pintype "passive"))
    )
    (net (code "174") (name "Net-(D117-K)") (class "Default")
      (node (ref "D117") (pin "2") (pinfunction "K_2") (pintype "passive"))
      (node (ref "R117") (pin "2") (pinfunction "2_2") (pintype "passive"))
    )
    (net (code "175") (name "Net-(D118-K)") (class "Default")
      (node (ref "D118") (pin "2") (pinfunction "K_2") (pintype "passive"))
      (node (ref "R118") (pin "2") (pinfunction "2_2") (pintype "passive"))
    )
    (net (code "176") (name "Net-(D119-K)") (class "Default")
      (node (ref "D119") (pin "2") (pinfunction "K_2") (pintype "passive"))
      (node (ref "R119") (pin "2") (pinfunction "2_2") (pintype "passive"))
    )
    (net (code "177") (name "Net-(D120-K)") (class "Default")
      (node (ref "D120") (pin "2") (pinfunction "K_2") (pintype "passive"))
      (node (ref "R120") (pin "2") (pinfunction "2_2") (pintype "passive"))
    )
    (net (code "178") (name "Net-(D121-K)") (class "Default")
      (node (ref "D121") (pin "2") (pinfunction "K_2") (pintype "passive"))
      (node (ref "R121") (pin "2") (pinfunction "2_2") (pintype "passive"))
    )
    (net (code "179") (name "Net-(D122-K)") (class "Default")
      (node (ref "D122") (pin "2") (pinfunction "K_2") (pintype "passive"))
      (node (ref "R122") (pin "2") (pinfunction "2_2") (pintype "passive"))
    )
    (net (code "180") (name "Net-(D123-K)") (class "Default")
      (node (ref "D123") (pin "2") (pinfunction "K_2") (pintype "passive"))
      (node (ref "R123") (pin "2") (pinfunction "2_2") (pintype "passive"))
    )
    (net (code "181") (name "Net-(D124-K)") (class "Default")
      (node (ref "D124") (pin "2") (pinfunction "K_2") (pintype "passive"))
      (node (ref "R124") (pin "2") (pinfunction "2_2") (pintype "passive"))
    )
    (net (code "182") (name "Net-(D125-K)") (class "Default")
      (node (ref "D125") (pin "2") (pinfunction "K_2") (pintype "passive"))
      (node (ref "R125") (pin "2") (pinfunction "2_2") (pintype "passive"))
    )
    (net (code "183") (name "Net-(D126-K)") (class "Default")
      (node (ref "D126") (pin "2") (pinfunction "K_2") (pintype "passive"))
      (node (ref "R126") (pin "2") (pinfunction "2_2") (pintype "passive"))
    )
    (net (code "184") (name "Net-(D127-K)") (class "Default")
      (node (ref "D127") (pin "2") (pinfunction "K_2") (pintype "passive"))
      (node (ref "R127") (pin "2") (pinfunction "2_2") (pintype "passive"))
    )
    (net (code "185") (name "Net-(D128-K)") (class "Default")
      (node (ref "D128") (pin "2") (pinfunction "K_2") (pintype "passive"))
      (node (ref "R128") (pin "2") (pinfunction "2_2") (pintype "passive"))
    )
    (net (code "186") (name "Net-(D129-K)") (class "Default")
      (node (ref "D129") (pin "2") (pinfunction "K_2") (pintype "passive"))
      (node (ref "R129") (pin "2") (pinfunction "2_2") (pintype "passive"))
    )
    (net (code "187") (name "Net-(D130-K)") (class "Default")
      (node (ref "D130") (pin "2") (pinfunction "K_2") (pintype "passive"))
      (node (ref "R130") (pin "2") (pinfunction "2_2") (pintype "passive"))
    )
    (net (code "188") (name "Net-(D131-K)") (class "Default")
      (node (ref "D131") (pin "2") (pinfunction "K_2") (pintype "passive"))
      (node (ref "R131") (pin "2") (pinfunction "2_2") (pintype "passive"))
    )
    (net (code "189") (name "Net-(D132-K)") (class "Default")
      (node (ref "D132") (pin "2") (pinfunction "K_2") (pintype "passive"))
      (node (ref "R132") (pin "2") (pinfunction "2_2") (pintype "passive"))
    )
    (net (code "190") (name "Net-(D133-K)") (class "Default")
      (node (ref "D133") (pin "2") (pinfunction "K_2") (pintype "passive"))
      (node (ref "R133") (pin "2") (pinfunction "2_2") (pintype "passive"))
    )
    (net (code "191") (name "Net-(D134-K)") (class "Default")
      (node (ref "D134") (pin "2") (pinfunction "K_2") (pintype "passive"))
      (node (ref "R134") (pin "2") (pinfunction "2_2") (pintype "passive"))
    )
    (net (code "192") (name "Net-(D135-K)") (class "Default")
      (node (ref "D135") (pin "2") (pinfunction "K_2") (pintype "passive"))
      (node (ref "R135") (pin "2") (pinfunction "2_2") (pintype "passive"))
    )
    (net (code "193") (name "Net-(D136-K)") (class "Default")
      (node (ref "D136") (pin "2") (pinfunction "K_2") (pintype "passive"))
      (node (ref "R136") (pin "2") (pinfunction "2_2") (pintype "passive"))
    )
    (net (code "194") (name "Net-(D137-K)") (class "Default")
      (node (ref "D137") (pin "2") (pinfunction "K_2") (pintype "passive"))
      (node (ref "R137") (pin "2") (pinfunction "2_2") (pintype "passive"))
    )
    (net (code "195") (name "Net-(D138-K)") (class "Default")
      (node (ref "D138") (pin "2") (pinfunction "K_2") (pintype "passive"))
      (node (ref "R138") (pin "2") (pinfunction "2_2") (pintype "passive"))
    )
    (net (code "196") (name "Net-(D139-K)") (class "Default")
      (node (ref "D139") (pin "2") (pinfunction "K_2") (pintype "passive"))
      (node (ref "R139") (pin "2") (pinfunction "2_2") (pintype "passive"))
    )
    (net (code "197") (name "Net-(D140-K)") (class "Default")
      (node (ref "D140") (pin "2") (pinfunction "K_2") (pintype "passive"))
      (node (ref "R140") (pin "2") (pinfunction "2_2") (pintype "passive"))
    )
    (net (code "198") (name "Net-(D141-K)") (class "Default")
      (node (ref "D141") (pin "2") (pinfunction "K_2") (pintype "passive"))
      (node (ref "R141") (pin "2") (pinfunction "2_2") (pintype "passive"))
    )
    (net (code "199") (name "Net-(D142-K)") (class "Default")
      (node (ref "D142") (pin "2") (pinfunction "K_2") (pintype "passive"))
      (node (ref "R142") (pin "2") (pinfunction "2_2") (pintype "passive"))
    )
    (net (code "200") (name "Net-(D143-K)") (class "Default")
      (node (ref "D143") (pin "2") (pinfunction "K_2") (pintype "passive"))
      (node (ref "R143") (pin "2") (pinfunction "2_2") (pintype "passive"))
    )
    (net (code "201") (name "Net-(D144-K)") (class "Default")
      (node (ref "D144") (pin "2") (pinfunction "K_2") (pintype "passive"))
      (node (ref "R144") (pin "2") (pinfunction "2_2") (pintype "passive"))
    )
    (net (code "202") (name "unconnected-(RL109-Pad4)") (class "Default")
      (node (ref "RL109") (pin "4") (pintype "passive"))
    )
    (net (code "203") (name "unconnected-(RL109-Pad5)") (class "Default")
      (node (ref "RL109") (pin "5") (pintype "passive"))
    )
    (net (code "204") (name "unconnected-(RL109-Pad6)") (class "Default")
      (node (ref "RL109") (pin "6") (pintype "passive"))
    )
    (net (code "205") (name "unconnected-(RL110-Pad4)") (class "Default")
      (node (ref "RL110") (pin "4") (pintype "passive"))
    )
    (net (code "206") (name "unconnected-(RL110-Pad5)") (class "Default")
      (node (ref "RL110") (pin "5") (pintype "passive"))
    )
    (net (code "207") (name "unconnected-(RL110-Pad6)") (class "Default")
      (node (ref "RL110") (pin "6") (pintype "passive"))
    )
    (net (code "208") (name "unconnected-(RL111-Pad4)") (class "Default")
      (node (ref "RL111") (pin "4") (pintype "passive"))
    )
    (net (code "209") (name "unconnected-(RL111-Pad5)") (class "Default")
      (node (ref "RL111") (pin "5") (pintype "passive"))
    )
    (net (code "210") (name "unconnected-(RL111-Pad6)") (class "Default")
      (node (ref "RL111") (pin "6") (pintype "passive"))
    )
    (net (code "211") (name "unconnected-(RL112-Pad4)") (class "Default")
      (node (ref "RL112") (pin "4") (pintype "passive"))
    )
    (net (code "212") (name "unconnected-(RL112-Pad5)") (class "Default")
      (node (ref "RL112") (pin "5") (pintype "passive"))
    )
    (net (code "213") (name "unconnected-(RL112-Pad6)") (class "Default")
      (node (ref "RL112") (pin "6") (pintype "passive"))
    )
    (net (code "214") (name "unconnected-(RL113-Pad4)") (class "Default")
      (node (ref "RL113") (pin "4") (pintype "passive"))
    )
    (net (code "215") (name "unconnected-(RL113-Pad5)") (class "Default")
      (node (ref "RL113") (pin "5") (pintype "passive"))
    )
    (net (code "216") (name "unconnected-(RL113-Pad6)") (class "Default")
      (node (ref "RL113") (pin "6") (pintype "passive"))
    )
    (net (code "217") (name "unconnected-(RL114-Pad4)") (class "Default")
      (node (ref "RL114") (pin "4") (pintype "passive"))
    )
    (net (code "218") (name "unconnected-(RL114-Pad5)") (class "Default")
      (node (ref "RL114") (pin "5") (pintype "passive"))
    )
    (net (code "219") (name "unconnected-(RL114-Pad6)") (class "Default")
      (node (ref "RL114") (pin "6") (pintype "passive"))
    )
    (net (code "220") (name "unconnected-(RL115-Pad4)") (class "Default")
      (node (ref "RL115") (pin "4") (pintype "passive"))
    )
    (net (code "221") (name "unconnected-(RL115-Pad5)") (class "Default")
      (node (ref "RL115") (pin "5") (pintype "passive"))
    )
    (net (code "222") (name "unconnected-(RL115-Pad6)") (class "Default")
      (node (ref "RL115") (pin "6") (pintype "passive"))
    )
    (net (code "223") (name "unconnected-(RL116-Pad4)") (class "Default")
      (node (ref "RL116") (pin "4") (pintype "passive"))
    )
    (net (code "224") (name "unconnected-(RL116-Pad5)") (class "Default")
      (node (ref "RL116") (pin "5") (pintype "passive"))
    )
    (net (code "225") (name "unconnected-(RL116-Pad6)") (class "Default")
      (node (ref "RL116") (pin "6") (pintype "passive"))
    )
    (net (code "226") (name "unconnected-(RL117-Pad4)") (class "Default")
      (node (ref "RL117") (pin "4") (pintype "passive"))
    )
    (net (code "227") (name "unconnected-(RL117-Pad5)") (class "Default")
      (node (ref "RL117") (pin "5") (pintype "passive"))
    )
    (net (code "228") (name "unconnected-(RL117-Pad6)") (class "Default")
      (node (ref "RL117") (pin "6") (pintype "passive"))
    )
    (net (code "229") (name "unconnected-(RL118-Pad4)") (class "Default")
      (node (ref "RL118") (pin "4") (pintype "passive"))
    )
    (net (code "230") (name "unconnected-(RL118-Pad5)") (class "Default")
      (node (ref "RL118") (pin "5") (pintype "passive"))
    )
    (net (code "231") (name "unconnected-(RL118-Pad6)") (class "Default")
      (node (ref "RL118") (pin "6") (pintype "passive"))
    )
    (net (code "232") (name "unconnected-(RL119-Pad4)") (class "Default")
      (node (ref "RL119") (pin "4") (pintype "passive"))
    )
    (net (code "233") (name "unconnected-(RL119-Pad5)") (class "Default")
      (node (ref "RL119") (pin "5") (pintype "passive"))
    )
    (net (code "234") (name "unconnected-(RL119-Pad6)") (class "Default")
      (node (ref "RL119") (pin "6") (pintype "passive"))
    )
    (net (code "235") (name "unconnected-(RL120-Pad4)") (class "Default")
      (node (ref "RL120") (pin "4") (pintype "passive"))
    )
    (net (code "236") (name "unconnected-(RL120-Pad5)") (class "Default")
      (node (ref "RL120") (pin "5") (pintype "passive"))
    )
    (net (code "237") (name "unconnected-(RL120-Pad6)") (class "Default")
      (node (ref "RL120") (pin "6") (pintype "passive"))
    )
    (net (code "238") (name "unconnected-(RL121-Pad4)") (class "Default")
      (node (ref "RL121") (pin "4") (pintype "passive"))
    )
    (net (code "239") (name "unconnected-(RL121-Pad5)") (class "Default")
      (node (ref "RL121") (pin "5") (pintype "passive"))
    )
    (net (code "240") (name "unconnected-(RL121-Pad6)") (class "Default")
      (node (ref "RL121") (pin "6") (pintype "passive"))
    )
    (net (code "241") (name "unconnected-(RL122-Pad4)") (class "Default")
      (node (ref "RL122") (pin "4") (pintype "passive"))
    )
    (net (code "242") (name "unconnected-(RL122-Pad5)") (class "Default")
      (node (ref "RL122") (pin "5") (pintype "passive"))
    )
    (net (code "243") (name "unconnected-(RL122-Pad6)") (class "Default")
      (node (ref "RL122") (pin "6") (pintype "passive"))
    )
    (net (code "244") (name "unconnected-(RL123-Pad4)") (class "Default")
      (node (ref "RL123") (pin "4") (pintype "passive"))
    )
    (net (code "245") (name "unconnected-(RL123-Pad5)") (class "Default")
      (node (ref "RL123") (pin "5") (pintype "passive"))
    )
    (net (code "246") (name "unconnected-(RL123-Pad6)") (class "Default")
      (node (ref "RL123") (pin "6") (pintype "passive"))
    )
    (net (code "247") (name "unconnected-(RL124-Pad4)") (class "Default")
      (node (ref "RL124") (pin "4") (pintype "passive"))
    )
    (net (code "248") (name "unconnected-(RL124-Pad5)") (class "Default")
      (node (ref "RL124") (pin "5") (pintype "passive"))
    )
    (net (code "249") (name "unconnected-(RL124-Pad6)") (class "Default")
      (node (ref "RL124") (pin "6") (pintype "passive"))
    )
    (net (code "250") (name "unconnected-(RL125-Pad4)") (class "Default")
      (node (ref "RL125") (pin "4") (pintype "passive"))
    )
    (net (code "251") (name "unconnected-(RL125-Pad5)") (class "Default")
      (node (ref "RL125") (pin "5") (pintype "passive"))
    )
    (net (code "252") (name "unconnected-(RL125-Pad6)") (class "Default")
      (node (ref "RL125") (pin "6") (pintype "passive"))
    )
    (net (code "253") (name "unconnected-(RL126-Pad4)") (class "Default")
      (node (ref "RL126") (pin "4") (pintype "passive"))
    )
    (net (code "254") (name "unconnected-(RL126-Pad5)") (class "Default")
      (node (ref "RL126") (pin "5") (pintype "passive"))
    )
    (net (code "255") (name "unconnected-(RL126-Pad6)") (class "Default")
      (node (ref "RL126") (pin "6") (pintype "passive"))
    )
    (net (code "256") (name "unconnected-(RL127-Pad4)") (class "Default")
      (node (ref "RL127") (pin "4") (pintype "passive"))
    )
    (net (code "257") (name "unconnected-(RL127-Pad5)") (class "Default")
      (node (ref "RL127") (pin "5") (pintype "passive"))
    )
    (net (code "258") (name "unconnected-(RL127-Pad6)") (class "Default")
      (node (ref "RL127") (pin "6") (pintype "passive"))
    )
    (net (code "259") (name "unconnected-(RL128-Pad4)") (class "Default")
      (node (ref "RL128") (pin "4") (pintype "passive"))
    )
    (net (code "260") (name "unconnected-(RL128-Pad5)") (class "Default")
      (node (ref "RL128") (pin "5") (pintype "passive"))
    )
    (net (code "261") (name "unconnected-(RL128-Pad6)") (class "Default")
      (node (ref "RL128") (pin "6") (pintype "passive"))
    )
    (net (code "262") (name "unconnected-(RL129-Pad4)") (class "Default")
      (node (ref "RL129") (pin "4") (pintype "passive"))
    )
    (net (code "263") (name "unconnected-(RL129-Pad5)") (class "Default")
      (node (ref "RL129") (pin "5") (pintype "passive"))
    )
    (net (code "264") (name "unconnected-(RL129-Pad6)") (class "Default")
      (node (ref "RL129") (pin "6") (pintype "passive"))
    )
    (net (code "265") (name "unconnected-(RL130-Pad4)") (class "Default")
      (node (ref "RL130") (pin "4") (pintype "passive"))
    )
    (net (code "266") (name "unconnected-(RL130-Pad5)") (class "Default")
      (node (ref "RL130") (pin "5") (pintype "passive"))
    )
    (net (code "267") (name "unconnected-(RL130-Pad6)") (class "Default")
      (node (ref "RL130") (pin "6") (pintype "passive"))
    )
    (net (code "268") (name "unconnected-(RL131-Pad4)") (class "Default")
      (node (ref "RL131") (pin "4") (pintype "passive"))
    )
    (net (code "269") (name "unconnected-(RL131-Pad5)") (class "Default")
      (node (ref "RL131") (pin "5") (pintype "passive"))
    )
    (net (code "270") (name "unconnected-(RL131-Pad6)") (class "Default")
      (node (ref "RL131") (pin "6") (pintype "passive"))
    )
    (net (code "271") (name "unconnected-(RL132-Pad4)") (class "Default")
      (node (ref "RL132") (pin "4") (pintype "passive"))
    )
    (net (code "272") (name "unconnected-(RL132-Pad5)") (class "Default")
      (node (ref "RL132") (pin "5") (pintype "passive"))
    )
    (net (code "273") (name "unconnected-(RL132-Pad6)") (class "Default")
      (node (ref "RL132") (pin "6") (pintype "passive"))
    )
    (net (code "274") (name "unconnected-(RL133-Pad4)") (class "Default")
      (node (ref "RL133") (pin "4") (pintype "passive"))
    )
    (net (code "275") (name "unconnected-(RL133-Pad5)") (class "Default")
      (node (ref "RL133") (pin "5") (pintype "passive"))
    )
    (net (code "276") (name "unconnected-(RL133-Pad6)") (class "Default")
      (node (ref "RL133") (pin "6") (pintype "passive"))
    )
    (net (code "277") (name "unconnected-(RL134-Pad4)") (class "Default")
      (node (ref "RL134") (pin "4") (pintype "passive"))
    )
    (net (code "278") (name "unconnected-(RL134-Pad5)") (class "Default")
      (node (ref "RL134") (pin "5") (pintype "passive"))
    )
    (net (code "279") (name "unconnected-(RL134-Pad6)") (class "Default")
      (node (ref "RL134") (pin "6") (pintype "passive"))
    )
    (net (code "280") (name "unconnected-(RL135-Pad4)") (class "Default")
      (node (ref "RL135") (pin "4") (pintype "passive"))
    )
    (net (code "281") (name "unconnected-(RL135-Pad5)") (class "Default")
      (node (ref "RL135") (pin "5") (pintype "passive"))
    )
    (net (code "282") (name "unconnected-(RL135-Pad6)") (class "Default")
      (node (ref "RL135") (pin "6") (pintype "passive"))
    )
    (net (code "283") (name "unconnected-(RL136-Pad4)") (class "Default")
      (node (ref "RL136") (pin "4") (pintype "passive"))
    )
    (net (code "284") (name "unconnected-(RL136-Pad5)") (class "Default")
      (node (ref "RL136") (pin "5") (pintype "passive"))
    )
    (net (code "285") (name "unconnected-(RL136-Pad6)") (class "Default")
      (node (ref "RL136") (pin "6") (pintype "passive"))
    )
    (net (code "286") (name "unconnected-(RL137-Pad4)") (class "Default")
      (node (ref "RL137") (pin "4") (pintype "passive"))
    )
    (net (code "287") (name "unconnected-(RL137-Pad5)") (class "Default")
      (node (ref "RL137") (pin "5") (pintype "passive"))
    )
    (net (code "288") (name "unconnected-(RL137-Pad6)") (class "Default")
      (node (ref "RL137") (pin "6") (pintype "passive"))
    )
    (net (code "289") (name "unconnected-(RL138-Pad4)") (class "Default")
      (node (ref "RL138") (pin "4") (pintype "passive"))
    )
    (net (code "290") (name "unconnected-(RL138-Pad5)") (class "Default")
      (node (ref "RL138") (pin "5") (pintype "passive"))
    )
    (net (code "291") (name "unconnected-(RL138-Pad6)") (class "Default")
      (node (ref "RL138") (pin "6") (pintype "passive"))
    )
    (net (code "292") (name "unconnected-(RL139-Pad4)") (class "Default")
      (node (ref "RL139") (pin "4") (pintype "passive"))
    )
    (net (code "293") (name "unconnected-(RL139-Pad5)") (class "Default")
      (node (ref "RL139") (pin "5") (pintype "passive"))
    )
    (net (code "294") (name "unconnected-(RL139-Pad6)") (class "Default")
      (node (ref "RL139") (pin "6") (pintype "passive"))
    )
    (net (code "295") (name "unconnected-(RL140-Pad4)") (class "Default")
      (node (ref "RL140") (pin "4") (pintype "passive"))
    )
    (net (code "296") (name "unconnected-(RL140-Pad5)") (class "Default")
      (node (ref "RL140") (pin "5") (pintype "passive"))
    )
    (net (code "297") (name "unconnected-(RL140-Pad6)") (class "Default")
      (node (ref "RL140") (pin "6") (pintype "passive"))
    )
    (net (code "298") (name "unconnected-(RL141-Pad4)") (class "Default")
      (node (ref "RL141") (pin "4") (pintype "passive"))
    )
    (net (code "299") (name "unconnected-(RL141-Pad5)") (class "Default")
      (node (ref "RL141") (pin "5") (pintype "passive"))
    )
    (net (code "300") (name "unconnected-(RL141-Pad6)") (class "Default")
      (node (ref "RL141") (pin "6") (pintype "passive"))
    )
    (net (code "301") (name "unconnected-(RL142-Pad4)") (class "Default")
      (node (ref "RL142") (pin "4") (pintype "passive"))
    )
    (net (code "302") (name "unconnected-(RL142-Pad5)") (class "Default")
      (node (ref "RL142") (pin "5") (pintype "passive"))
    )
    (net (code "303") (name "unconnected-(RL142-Pad6)") (class "Default")
      (node (ref "RL142") (pin "6") (pintype "passive"))
    )
    (net (code "304") (name "unconnected-(RL143-Pad4)") (class "Default")
      (node (ref "RL143") (pin "4") (pintype "passive"))
    )
    (net (code "305") (name "unconnected-(RL143-Pad5)") (class "Default")
      (node (ref "RL143") (pin "5") (pintype "passive"))
    )
    (net (code "306") (name "unconnected-(RL143-Pad6)") (class "Default")
      (node (ref "RL143") (pin "6") (pintype "passive"))
    )
    (net (code "307") (name "unconnected-(RL144-Pad4)") (class "Default")
      (node (ref "RL144") (pin "4") (pintype "passive"))
    )
    (net (code "308") (name "unconnected-(RL144-Pad5)") (class "Default")
      (node (ref "RL144") (pin "5") (pintype "passive"))
    )
    (net (code "309") (name "unconnected-(RL144-Pad6)") (class "Default")
      (node (ref "RL144") (pin "6") (pintype "passive"))
    )
  )
)
